# SW_12.net
KiCad netlist of a schematic drawn in Altium Designer
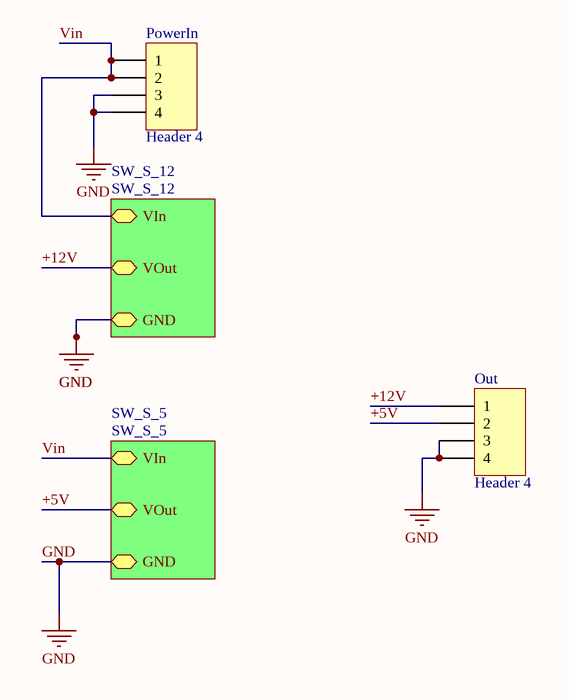
[diagram p0: SW 12.schdoc]

(export (version "E")
  (design (tool "Eeschema 10.0.6"))
  (components
    (comp (ref "Out")
      (value "Header 4")
      (footprint "HDR1X4")
      (description "Header, 4-Pin")
      (fields (field (name "PUBLISHER") "Altium Limited"))
      (libsource (lib "Miscellaneous Connectors") (part "Header 4"))
    )
    (comp (ref "PowerIn")
      (value "Header 4")
      (footprint "HDR1X4")
      (description "Header, 4-Pin")
      (fields (field (name "PUBLISHER") "Altium Limited"))
      (libsource (lib "Miscellaneous Connectors") (part "Header 4"))
    )
  )
  (nets
    (net (code "1") (name "/+5V") (class "Default")
      (node (ref "Out") (pin "2") (pinfunction "2_2") (pintype "passive"))
    )
    (net (code "2") (name "/+12V") (class "Default")
      (node (ref "Out") (pin "1") (pinfunction "1_1") (pintype "passive"))
    )
    (net (code "3") (name "/Vin") (class "Default")
      (node (ref "PowerIn") (pin "1") (pinfunction "1_1") (pintype "passive"))
      (node (ref "PowerIn") (pin "2") (pinfunction "2_2") (pintype "passive"))
    )
    (net (code "4") (name "GND") (class "Default")
      (node (ref "Out") (pin "3") (pinfunction "3_3") (pintype "passive"))
      (node (ref "Out") (pin "4") (pinfunction "4_4") (pintype "passive"))
      (node (ref "PowerIn") (pin "3") (pinfunction "3_3") (pintype "passive"))
      (node (ref "PowerIn") (pin "4") (pinfunction "4_4") (pintype "passive"))
    )
  )
)
